# as14120_x31_fpga_ttl.net
KiCad netlist of a schematic drawn in Altium Designer
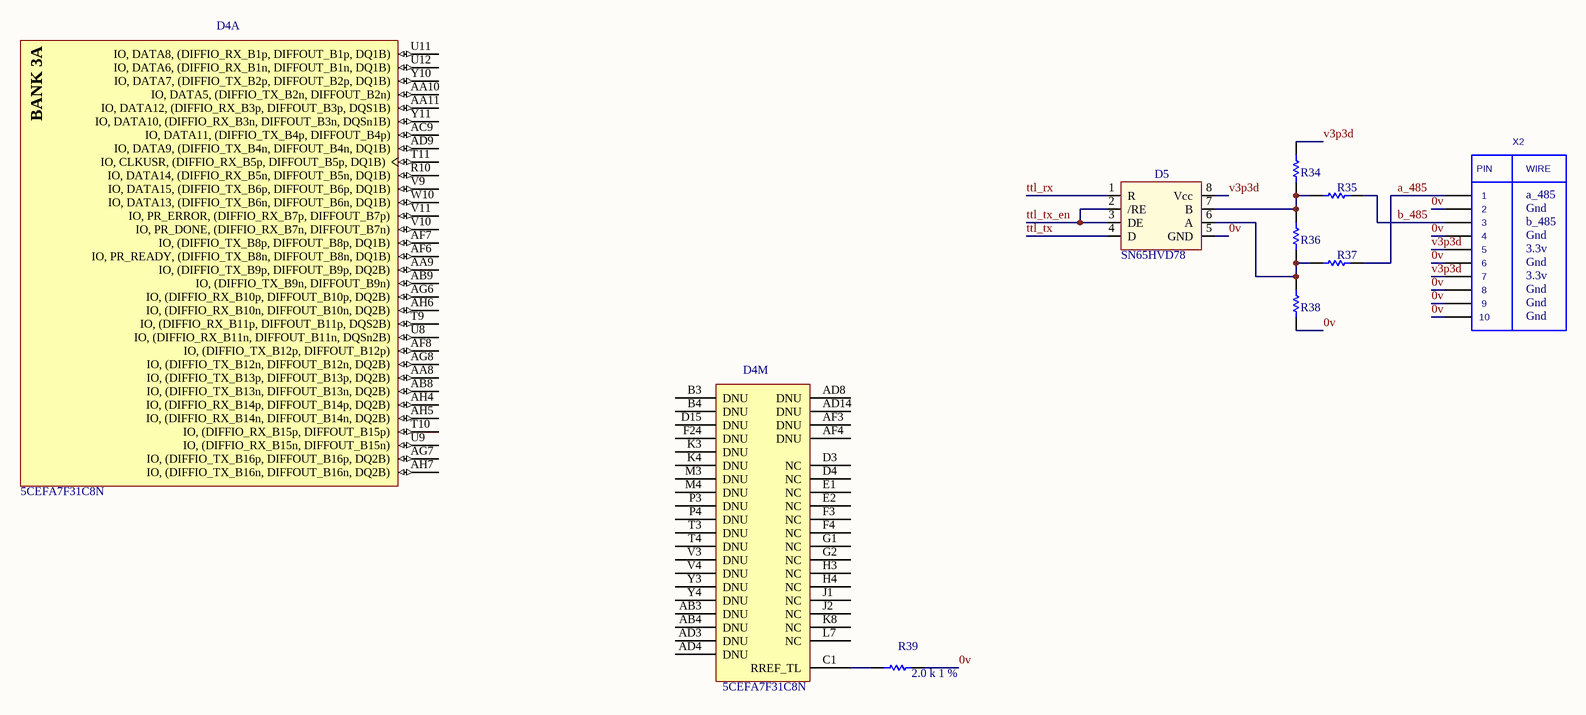
[diagram p0: as14120_x31_fpga_ttl.SchDoc]

(export (version "E")
  (design (tool "Eeschema 10.0.6"))
  (components
    (comp (ref "D4")
      (value "5CEFA7F31C8N")
      (footprint "ALTR-896-FBGA-2000A")
      (fields (field (name "MANUFACTURER") "Altera"))
      (libsource (lib "Altera Cyclone V E") (part "5CEFA7F31C8N"))
    )
    (comp (ref "D5") (value "SN65HVD78") (footprint "8S1_M") (libsource (lib "as14120") (part "SN65HVD78")))
    (comp (ref "R34")
      (value "1K 1% 0805(2012)")
      (footprint "RESC0805(2012)_L")
      (description "1K 0.125W 1% 0805 (2012 Metric)  SMD")
      (fields (field (name "TOLERANCE") "1 %") (field (name "POWER") "0.125 W"))
      (libsource (lib "as14120") (part "RES_0805"))
    )
    (comp (ref "R35")
      (value "1K 1% 0805(2012)")
      (footprint "RESC0805(2012)_L")
      (description "1K 0.125W 1% 0805 (2012 Metric)  SMD")
      (fields (field (name "TOLERANCE") "1 %") (field (name "POWER") "0.125 W"))
      (libsource (lib "as14120") (part "RES_0805"))
    )
    (comp (ref "R36")
      (value "1K 1% 0805(2012)")
      (footprint "RESC0805(2012)_L")
      (description "1K 0.125W 1% 0805 (2012 Metric)  SMD")
      (fields (field (name "TOLERANCE") "1 %") (field (name "POWER") "0.125 W"))
      (libsource (lib "as14120") (part "RES_0805"))
    )
    (comp (ref "R37")
      (value "1K 1% 0805(2012)")
      (footprint "RESC0805(2012)_L")
      (description "1K 0.125W 1% 0805 (2012 Metric)  SMD")
      (fields (field (name "TOLERANCE") "1 %") (field (name "POWER") "0.125 W"))
      (libsource (lib "as14120") (part "RES_0805"))
    )
    (comp (ref "R38")
      (value "1K 1% 0805(2012)")
      (footprint "RESC0805(2012)_L")
      (description "1K 0.125W 1% 0805 (2012 Metric)  SMD")
      (fields (field (name "TOLERANCE") "1 %") (field (name "POWER") "0.125 W"))
      (libsource (lib "as14120") (part "RES_0805"))
    )
    (comp (ref "R39")
      (value "2.0 k")
      (footprint "RESC0805(2012)_L")
      (description "1K 0.125W 1% 0805 (2012 Metric)  SMD")
      (fields
        (field (name "TOLERANCE") "1 %")
        (field (name "POWER") "0.125 W")
        (field (name "Comment") "1K 1% 0805(2012)")
      )
      (libsource (lib "as14120") (part "RES_0805"))
    )
    (comp (ref "X2") (value "IDC10") (footprint "IDC10M") (libsource (lib "alexsb") (part "IDC10")))
  )
  (nets
    (net (code "1") (name "/0v") (class "Default")
      (node (ref "D5") (pin "5") (pinfunction "GND_5") (pintype "passive"))
      (node (ref "R38") (pin "1") (pinfunction "1_1") (pintype "passive"))
      (node (ref "R39") (pin "2") (pinfunction "2_2") (pintype "passive"))
      (node (ref "X2") (pin "10") (pintype "passive"))
      (node (ref "X2") (pin "2") (pintype "passive"))
      (node (ref "X2") (pin "4") (pintype "passive"))
      (node (ref "X2") (pin "6") (pintype "passive"))
      (node (ref "X2") (pin "8") (pintype "passive"))
      (node (ref "X2") (pin "9") (pintype "passive"))
    )
    (net (code "2") (name "/a_485") (class "Default")
      (node (ref "R37") (pin "2") (pinfunction "2_2") (pintype "passive"))
      (node (ref "X2") (pin "1") (pintype "passive"))
    )
    (net (code "3") (name "/b_485") (class "Default")
      (node (ref "R35") (pin "2") (pinfunction "2_2") (pintype "passive"))
      (node (ref "X2") (pin "3") (pintype "passive"))
    )
    (net (code "4") (name "/ttl_rx") (class "Default")
      (node (ref "D5") (pin "1") (pinfunction "R_1") (pintype "passive"))
    )
    (net (code "5") (name "/ttl_tx") (class "Default")
      (node (ref "D5") (pin "4") (pinfunction "D_4") (pintype "passive"))
    )
    (net (code "6") (name "/ttl_tx_en") (class "Default")
      (node (ref "D5") (pin "2") (pinfunction "/RE_2") (pintype "passive"))
      (node (ref "D5") (pin "3") (pinfunction "DE_3") (pintype "passive"))
    )
    (net (code "7") (name "/v3p3d") (class "Default")
      (node (ref "D5") (pin "8") (pinfunction "Vcc_8") (pintype "passive"))
      (node (ref "R34") (pin "2") (pinfunction "2_2") (pintype "passive"))
      (node (ref "X2") (pin "5") (pintype "passive"))
      (node (ref "X2") (pin "7") (pintype "passive"))
    )
    (net (code "8") (name "Net-(D4M-RREF_TL)") (class "Default")
      (node (ref "D4") (pin "C1") (pinfunction "RREF_TL_C1") (pintype "passive"))
      (node (ref "R39") (pin "1") (pinfunction "1_1") (pintype "passive"))
    )
    (net (code "9") (name "Net-(D5-A)") (class "Default")
      (node (ref "D5") (pin "6") (pinfunction "A_6") (pintype "passive"))
      (node (ref "R36") (pin "1") (pinfunction "1_1") (pintype "passive"))
      (node (ref "R37") (pin "1") (pinfunction "1_1") (pintype "passive"))
      (node (ref "R38") (pin "2") (pinfunction "2_2") (pintype "passive"))
    )
    (net (code "10") (name "Net-(D5-B)") (class "Default")
      (node (ref "D5") (pin "7") (pinfunction "B_7") (pintype "passive"))
      (node (ref "R34") (pin "1") (pinfunction "1_1") (pintype "passive"))
      (node (ref "R35") (pin "1") (pinfunction "1_1") (pintype "passive"))
      (node (ref "R36") (pin "2") (pinfunction "2_2") (pintype "passive"))
    )
    (net (code "11") (name "unconnected-(D4A-IO,_(DIFFIO_RX_B10n,_DIFFOUT_B10n,_DQ2B)-PadAH6)") (class "Default")
      (node (ref "D4") (pin "AH6") (pinfunction "IO,_(DIFFIO_RX_B10n,_DIFFOUT_B10n,_DQ2B)_AH6") (pintype "bidirectional"))
    )
    (net (code "12") (name "unconnected-(D4A-IO,_(DIFFIO_RX_B10p,_DIFFOUT_B10p,_DQ2B)-PadAG6)") (class "Default")
      (node (ref "D4") (pin "AG6") (pinfunction "IO,_(DIFFIO_RX_B10p,_DIFFOUT_B10p,_DQ2B)_AG6") (pintype "bidirectional"))
    )
    (net (code "13") (name "unconnected-(D4A-IO,_(DIFFIO_RX_B11n,_DIFFOUT_B11n,_DQSn2B)-PadU8)") (class "Default")
      (node (ref "D4") (pin "U8") (pinfunction "IO,_(DIFFIO_RX_B11n,_DIFFOUT_B11n,_DQSn2B)_U8") (pintype "bidirectional"))
    )
    (net (code "14") (name "unconnected-(D4A-IO,_(DIFFIO_RX_B11p,_DIFFOUT_B11p,_DQS2B)-PadT9)") (class "Default")
      (node (ref "D4") (pin "T9") (pinfunction "IO,_(DIFFIO_RX_B11p,_DIFFOUT_B11p,_DQS2B)_T9") (pintype "bidirectional"))
    )
    (net (code "15") (name "unconnected-(D4A-IO,_(DIFFIO_RX_B14n,_DIFFOUT_B14n,_DQ2B)-PadAH5)") (class "Default")
      (node (ref "D4") (pin "AH5") (pinfunction "IO,_(DIFFIO_RX_B14n,_DIFFOUT_B14n,_DQ2B)_AH5") (pintype "bidirectional"))
    )
    (net (code "16") (name "unconnected-(D4A-IO,_(DIFFIO_RX_B14p,_DIFFOUT_B14p,_DQ2B)-PadAH4)") (class "Default")
      (node (ref "D4") (pin "AH4") (pinfunction "IO,_(DIFFIO_RX_B14p,_DIFFOUT_B14p,_DQ2B)_AH4") (pintype "bidirectional"))
    )
    (net (code "17") (name "unconnected-(D4A-IO,_(DIFFIO_RX_B15n,_DIFFOUT_B15n)-PadU9)") (class "Default")
      (node (ref "D4") (pin "U9") (pinfunction "IO,_(DIFFIO_RX_B15n,_DIFFOUT_B15n)_U9") (pintype "bidirectional"))
    )
    (net (code "18") (name "unconnected-(D4A-IO,_(DIFFIO_RX_B15p,_DIFFOUT_B15p)-PadT10)") (class "Default")
      (node (ref "D4") (pin "T10") (pinfunction "IO,_(DIFFIO_RX_B15p,_DIFFOUT_B15p)_T10") (pintype "bidirectional"))
    )
    (net (code "19") (name "unconnected-(D4A-IO,_(DIFFIO_TX_B8p,_DIFFOUT_B8p,_DQ1B)-PadAF7)") (class "Default")
      (node (ref "D4") (pin "AF7") (pinfunction "IO,_(DIFFIO_TX_B8p,_DIFFOUT_B8p,_DQ1B)_AF7") (pintype "bidirectional"))
    )
    (net (code "20") (name "unconnected-(D4A-IO,_(DIFFIO_TX_B9n,_DIFFOUT_B9n)-PadAB9)") (class "Default")
      (node (ref "D4") (pin "AB9") (pinfunction "IO,_(DIFFIO_TX_B9n,_DIFFOUT_B9n)_AB9") (pintype "bidirectional"))
    )
    (net (code "21") (name "unconnected-(D4A-IO,_(DIFFIO_TX_B9p,_DIFFOUT_B9p,_DQ2B)-PadAA9)") (class "Default")
      (node (ref "D4") (pin "AA9") (pinfunction "IO,_(DIFFIO_TX_B9p,_DIFFOUT_B9p,_DQ2B)_AA9") (pintype "bidirectional"))
    )
    (net (code "22") (name "unconnected-(D4A-IO,_(DIFFIO_TX_B12n,_DIFFOUT_B12n,_DQ2B)-PadAG8)") (class "Default")
      (node (ref "D4") (pin "AG8") (pinfunction "IO,_(DIFFIO_TX_B12n,_DIFFOUT_B12n,_DQ2B)_AG8") (pintype "bidirectional"))
    )
    (net (code "23") (name "unconnected-(D4A-IO,_(DIFFIO_TX_B12p,_DIFFOUT_B12p)-PadAF8)") (class "Default")
      (node (ref "D4") (pin "AF8") (pinfunction "IO,_(DIFFIO_TX_B12p,_DIFFOUT_B12p)_AF8") (pintype "bidirectional"))
    )
    (net (code "24") (name "unconnected-(D4A-IO,_(DIFFIO_TX_B13n,_DIFFOUT_B13n,_DQ2B)-PadAB8)") (class "Default")
      (node (ref "D4") (pin "AB8") (pinfunction "IO,_(DIFFIO_TX_B13n,_DIFFOUT_B13n,_DQ2B)_AB8") (pintype "bidirectional"))
    )
    (net (code "25") (name "unconnected-(D4A-IO,_(DIFFIO_TX_B13p,_DIFFOUT_B13p,_DQ2B)-PadAA8)") (class "Default")
      (node (ref "D4") (pin "AA8") (pinfunction "IO,_(DIFFIO_TX_B13p,_DIFFOUT_B13p,_DQ2B)_AA8") (pintype "bidirectional"))
    )
    (net (code "26") (name "unconnected-(D4A-IO,_(DIFFIO_TX_B16n,_DIFFOUT_B16n,_DQ2B)-PadAH7)") (class "Default")
      (node (ref "D4") (pin "AH7") (pinfunction "IO,_(DIFFIO_TX_B16n,_DIFFOUT_B16n,_DQ2B)_AH7") (pintype "bidirectional"))
    )
    (net (code "27") (name "unconnected-(D4A-IO,_(DIFFIO_TX_B16p,_DIFFOUT_B16p,_DQ2B)-PadAG7)") (class "Default")
      (node (ref "D4") (pin "AG7") (pinfunction "IO,_(DIFFIO_TX_B16p,_DIFFOUT_B16p,_DQ2B)_AG7") (pintype "bidirectional"))
    )
    (net (code "28") (name "unconnected-(D4A-IO,_CLKUSR,_(DIFFIO_RX_B5p,_DIFFOUT_B5p,_DQ1B)-PadT11)") (class "Default")
      (node (ref "D4") (pin "T11") (pinfunction "IO,_CLKUSR,_(DIFFIO_RX_B5p,_DIFFOUT_B5p,_DQ1B)_T11") (pintype "bidirectional"))
    )
    (net (code "29") (name "unconnected-(D4A-IO,_DATA5,_(DIFFIO_TX_B2n,_DIFFOUT_B2n)-PadAA10)") (class "Default")
      (node (ref "D4") (pin "AA10") (pinfunction "IO,_DATA5,_(DIFFIO_TX_B2n,_DIFFOUT_B2n)_AA10") (pintype "bidirectional"))
    )
    (net (code "30") (name "unconnected-(D4A-IO,_DATA6,_(DIFFIO_RX_B1n,_DIFFOUT_B1n,_DQ1B)-PadU12)") (class "Default")
      (node (ref "D4") (pin "U12") (pinfunction "IO,_DATA6,_(DIFFIO_RX_B1n,_DIFFOUT_B1n,_DQ1B)_U12") (pintype "bidirectional"))
    )
    (net (code "31") (name "unconnected-(D4A-IO,_DATA7,_(DIFFIO_TX_B2p,_DIFFOUT_B2p,_DQ1B)-PadY10)") (class "Default")
      (node (ref "D4") (pin "Y10") (pinfunction "IO,_DATA7,_(DIFFIO_TX_B2p,_DIFFOUT_B2p,_DQ1B)_Y10") (pintype "bidirectional"))
    )
    (net (code "32") (name "unconnected-(D4A-IO,_DATA8,_(DIFFIO_RX_B1p,_DIFFOUT_B1p,_DQ1B)-PadU11)") (class "Default")
      (node (ref "D4") (pin "U11") (pinfunction "IO,_DATA8,_(DIFFIO_RX_B1p,_DIFFOUT_B1p,_DQ1B)_U11") (pintype "bidirectional"))
    )
    (net (code "33") (name "unconnected-(D4A-IO,_DATA9,_(DIFFIO_TX_B4n,_DIFFOUT_B4n,_DQ1B)-PadAD9)") (class "Default")
      (node (ref "D4") (pin "AD9") (pinfunction "IO,_DATA9,_(DIFFIO_TX_B4n,_DIFFOUT_B4n,_DQ1B)_AD9") (pintype "bidirectional"))
    )
    (net (code "34") (name "unconnected-(D4A-IO,_DATA10,_(DIFFIO_RX_B3n,_DIFFOUT_B3n,_DQSn1B)-PadY11)") (class "Default")
      (node (ref "D4") (pin "Y11") (pinfunction "IO,_DATA10,_(DIFFIO_RX_B3n,_DIFFOUT_B3n,_DQSn1B)_Y11") (pintype "bidirectional"))
    )
    (net (code "35") (name "unconnected-(D4A-IO,_DATA11,_(DIFFIO_TX_B4p,_DIFFOUT_B4p)-PadAC9)") (class "Default")
      (node (ref "D4") (pin "AC9") (pinfunction "IO,_DATA11,_(DIFFIO_TX_B4p,_DIFFOUT_B4p)_AC9") (pintype "bidirectional"))
    )
    (net (code "36") (name "unconnected-(D4A-IO,_DATA12,_(DIFFIO_RX_B3p,_DIFFOUT_B3p,_DQS1B)-PadAA11)") (class "Default")
      (node (ref "D4") (pin "AA11") (pinfunction "IO,_DATA12,_(DIFFIO_RX_B3p,_DIFFOUT_B3p,_DQS1B)_AA11") (pintype "bidirectional"))
    )
    (net (code "37") (name "unconnected-(D4A-IO,_DATA13,_(DIFFIO_TX_B6n,_DIFFOUT_B6n,_DQ1B)-PadW10)") (class "Default")
      (node (ref "D4") (pin "W10") (pinfunction "IO,_DATA13,_(DIFFIO_TX_B6n,_DIFFOUT_B6n,_DQ1B)_W10") (pintype "bidirectional"))
    )
    (net (code "38") (name "unconnected-(D4A-IO,_DATA14,_(DIFFIO_RX_B5n,_DIFFOUT_B5n,_DQ1B)-PadR10)") (class "Default")
      (node (ref "D4") (pin "R10") (pinfunction "IO,_DATA14,_(DIFFIO_RX_B5n,_DIFFOUT_B5n,_DQ1B)_R10") (pintype "bidirectional"))
    )
    (net (code "39") (name "unconnected-(D4A-IO,_DATA15,_(DIFFIO_TX_B6p,_DIFFOUT_B6p,_DQ1B)-PadV9)") (class "Default")
      (node (ref "D4") (pin "V9") (pinfunction "IO,_DATA15,_(DIFFIO_TX_B6p,_DIFFOUT_B6p,_DQ1B)_V9") (pintype "bidirectional"))
    )
    (net (code "40") (name "unconnected-(D4A-IO,_PR_DONE,_(DIFFIO_RX_B7n,_DIFFOUT_B7n)-PadV10)") (class "Default")
      (node (ref "D4") (pin "V10") (pinfunction "IO,_PR_DONE,_(DIFFIO_RX_B7n,_DIFFOUT_B7n)_V10") (pintype "bidirectional"))
    )
    (net (code "41") (name "unconnected-(D4A-IO,_PR_ERROR,_(DIFFIO_RX_B7p,_DIFFOUT_B7p)-PadV11)") (class "Default")
      (node (ref "D4") (pin "V11") (pinfunction "IO,_PR_ERROR,_(DIFFIO_RX_B7p,_DIFFOUT_B7p)_V11") (pintype "bidirectional"))
    )
    (net (code "42") (name "unconnected-(D4A-IO,_PR_READY,_(DIFFIO_TX_B8n,_DIFFOUT_B8n,_DQ1B)-PadAF6)") (class "Default")
      (node (ref "D4") (pin "AF6") (pinfunction "IO,_PR_READY,_(DIFFIO_TX_B8n,_DIFFOUT_B8n,_DQ1B)_AF6") (pintype "bidirectional"))
    )
    (net (code "43") (name "unconnected-(D4M-DNU-PadAB3)") (class "Default")
      (node (ref "D4") (pin "AB3") (pinfunction "DNU_AB3") (pintype "passive"))
    )
    (net (code "44") (name "unconnected-(D4M-DNU-PadAB4)") (class "Default")
      (node (ref "D4") (pin "AB4") (pinfunction "DNU_AB4") (pintype "passive"))
    )
    (net (code "45") (name "unconnected-(D4M-DNU-PadAD3)") (class "Default")
      (node (ref "D4") (pin "AD3") (pinfunction "DNU_AD3") (pintype "passive"))
    )
    (net (code "46") (name "unconnected-(D4M-DNU-PadAD4)") (class "Default")
      (node (ref "D4") (pin "AD4") (pinfunction "DNU_AD4") (pintype "passive"))
    )
    (net (code "47") (name "unconnected-(D4M-DNU-PadAD8)") (class "Default")
      (node (ref "D4") (pin "AD8") (pinfunction "DNU_AD8") (pintype "passive"))
    )
    (net (code "48") (name "unconnected-(D4M-DNU-PadAD14)") (class "Default")
      (node (ref "D4") (pin "AD14") (pinfunction "DNU_AD14") (pintype "passive"))
    )
    (net (code "49") (name "unconnected-(D4M-DNU-PadAF3)") (class "Default")
      (node (ref "D4") (pin "AF3") (pinfunction "DNU_AF3") (pintype "passive"))
    )
    (net (code "50") (name "unconnected-(D4M-DNU-PadAF4)") (class "Default")
      (node (ref "D4") (pin "AF4") (pinfunction "DNU_AF4") (pintype "passive"))
    )
    (net (code "51") (name "unconnected-(D4M-DNU-PadB3)") (class "Default")
      (node (ref "D4") (pin "B3") (pinfunction "DNU_B3") (pintype "passive"))
    )
    (net (code "52") (name "unconnected-(D4M-DNU-PadB4)") (class "Default")
      (node (ref "D4") (pin "B4") (pinfunction "DNU_B4") (pintype "passive"))
    )
    (net (code "53") (name "unconnected-(D4M-DNU-PadD15)") (class "Default")
      (node (ref "D4") (pin "D15") (pinfunction "DNU_D15") (pintype "passive"))
    )
    (net (code "54") (name "unconnected-(D4M-DNU-PadF24)") (class "Default")
      (node (ref "D4") (pin "F24") (pinfunction "DNU_F24") (pintype "passive"))
    )
    (net (code "55") (name "unconnected-(D4M-DNU-PadK3)") (class "Default")
      (node (ref "D4") (pin "K3") (pinfunction "DNU_K3") (pintype "passive"))
    )
    (net (code "56") (name "unconnected-(D4M-DNU-PadK4)") (class "Default")
      (node (ref "D4") (pin "K4") (pinfunction "DNU_K4") (pintype "passive"))
    )
    (net (code "57") (name "unconnected-(D4M-DNU-PadM3)") (class "Default")
      (node (ref "D4") (pin "M3") (pinfunction "DNU_M3") (pintype "passive"))
    )
    (net (code "58") (name "unconnected-(D4M-DNU-PadM4)") (class "Default")
      (node (ref "D4") (pin "M4") (pinfunction "DNU_M4") (pintype "passive"))
    )
    (net (code "59") (name "unconnected-(D4M-DNU-PadP3)") (class "Default")
      (node (ref "D4") (pin "P3") (pinfunction "DNU_P3") (pintype "passive"))
    )
    (net (code "60") (name "unconnected-(D4M-DNU-PadP4)") (class "Default")
      (node (ref "D4") (pin "P4") (pinfunction "DNU_P4") (pintype "passive"))
    )
    (net (code "61") (name "unconnected-(D4M-DNU-PadT3)") (class "Default")
      (node (ref "D4") (pin "T3") (pinfunction "DNU_T3") (pintype "passive"))
    )
    (net (code "62") (name "unconnected-(D4M-DNU-PadT4)") (class "Default")
      (node (ref "D4") (pin "T4") (pinfunction "DNU_T4") (pintype "passive"))
    )
    (net (code "63") (name "unconnected-(D4M-DNU-PadV3)") (class "Default")
      (node (ref "D4") (pin "V3") (pinfunction "DNU_V3") (pintype "passive"))
    )
    (net (code "64") (name "unconnected-(D4M-DNU-PadV4)") (class "Default")
      (node (ref "D4") (pin "V4") (pinfunction "DNU_V4") (pintype "passive"))
    )
    (net (code "65") (name "unconnected-(D4M-DNU-PadY3)") (class "Default")
      (node (ref "D4") (pin "Y3") (pinfunction "DNU_Y3") (pintype "passive"))
    )
    (net (code "66") (name "unconnected-(D4M-DNU-PadY4)") (class "Default")
      (node (ref "D4") (pin "Y4") (pinfunction "DNU_Y4") (pintype "passive"))
    )
    (net (code "67") (name "unconnected-(D4M-NC-PadD3)") (class "Default")
      (node (ref "D4") (pin "D3") (pinfunction "NC_D3") (pintype "passive"))
    )
    (net (code "68") (name "unconnected-(D4M-NC-PadD4)") (class "Default")
      (node (ref "D4") (pin "D4") (pinfunction "NC_D4") (pintype "passive"))
    )
    (net (code "69") (name "unconnected-(D4M-NC-PadE1)") (class "Default")
      (node (ref "D4") (pin "E1") (pinfunction "NC_E1") (pintype "passive"))
    )
    (net (code "70") (name "unconnected-(D4M-NC-PadE2)") (class "Default")
      (node (ref "D4") (pin "E2") (pinfunction "NC_E2") (pintype "passive"))
    )
    (net (code "71") (name "unconnected-(D4M-NC-PadF3)") (class "Default")
      (node (ref "D4") (pin "F3") (pinfunction "NC_F3") (pintype "passive"))
    )
    (net (code "72") (name "unconnected-(D4M-NC-PadF4)") (class "Default")
      (node (ref "D4") (pin "F4") (pinfunction "NC_F4") (pintype "passive"))
    )
    (net (code "73") (name "unconnected-(D4M-NC-PadG1)") (class "Default")
      (node (ref "D4") (pin "G1") (pinfunction "NC_G1") (pintype "passive"))
    )
    (net (code "74") (name "unconnected-(D4M-NC-PadG2)") (class "Default")
      (node (ref "D4") (pin "G2") (pinfunction "NC_G2") (pintype "passive"))
    )
    (net (code "75") (name "unconnected-(D4M-NC-PadH3)") (class "Default")
      (node (ref "D4") (pin "H3") (pinfunction "NC_H3") (pintype "passive"))
    )
    (net (code "76") (name "unconnected-(D4M-NC-PadH4)") (class "Default")
      (node (ref "D4") (pin "H4") (pinfunction "NC_H4") (pintype "passive"))
    )
    (net (code "77") (name "unconnected-(D4M-NC-PadJ1)") (class "Default")
      (node (ref "D4") (pin "J1") (pinfunction "NC_J1") (pintype "passive"))
    )
    (net (code "78") (name "unconnected-(D4M-NC-PadJ2)") (class "Default")
      (node (ref "D4") (pin "J2") (pinfunction "NC_J2") (pintype "passive"))
    )
    (net (code "79") (name "unconnected-(D4M-NC-PadK8)") (class "Default")
      (node (ref "D4") (pin "K8") (pinfunction "NC_K8") (pintype "passive"))
    )
    (net (code "80") (name "unconnected-(D4M-NC-PadL7)") (class "Default")
      (node (ref "D4") (pin "L7") (pinfunction "NC_L7") (pintype "passive"))
    )
  )
)
